# SAMD21_Xplained_Pro_EDBG.net
KiCad netlist of a schematic drawn in Altium Designer
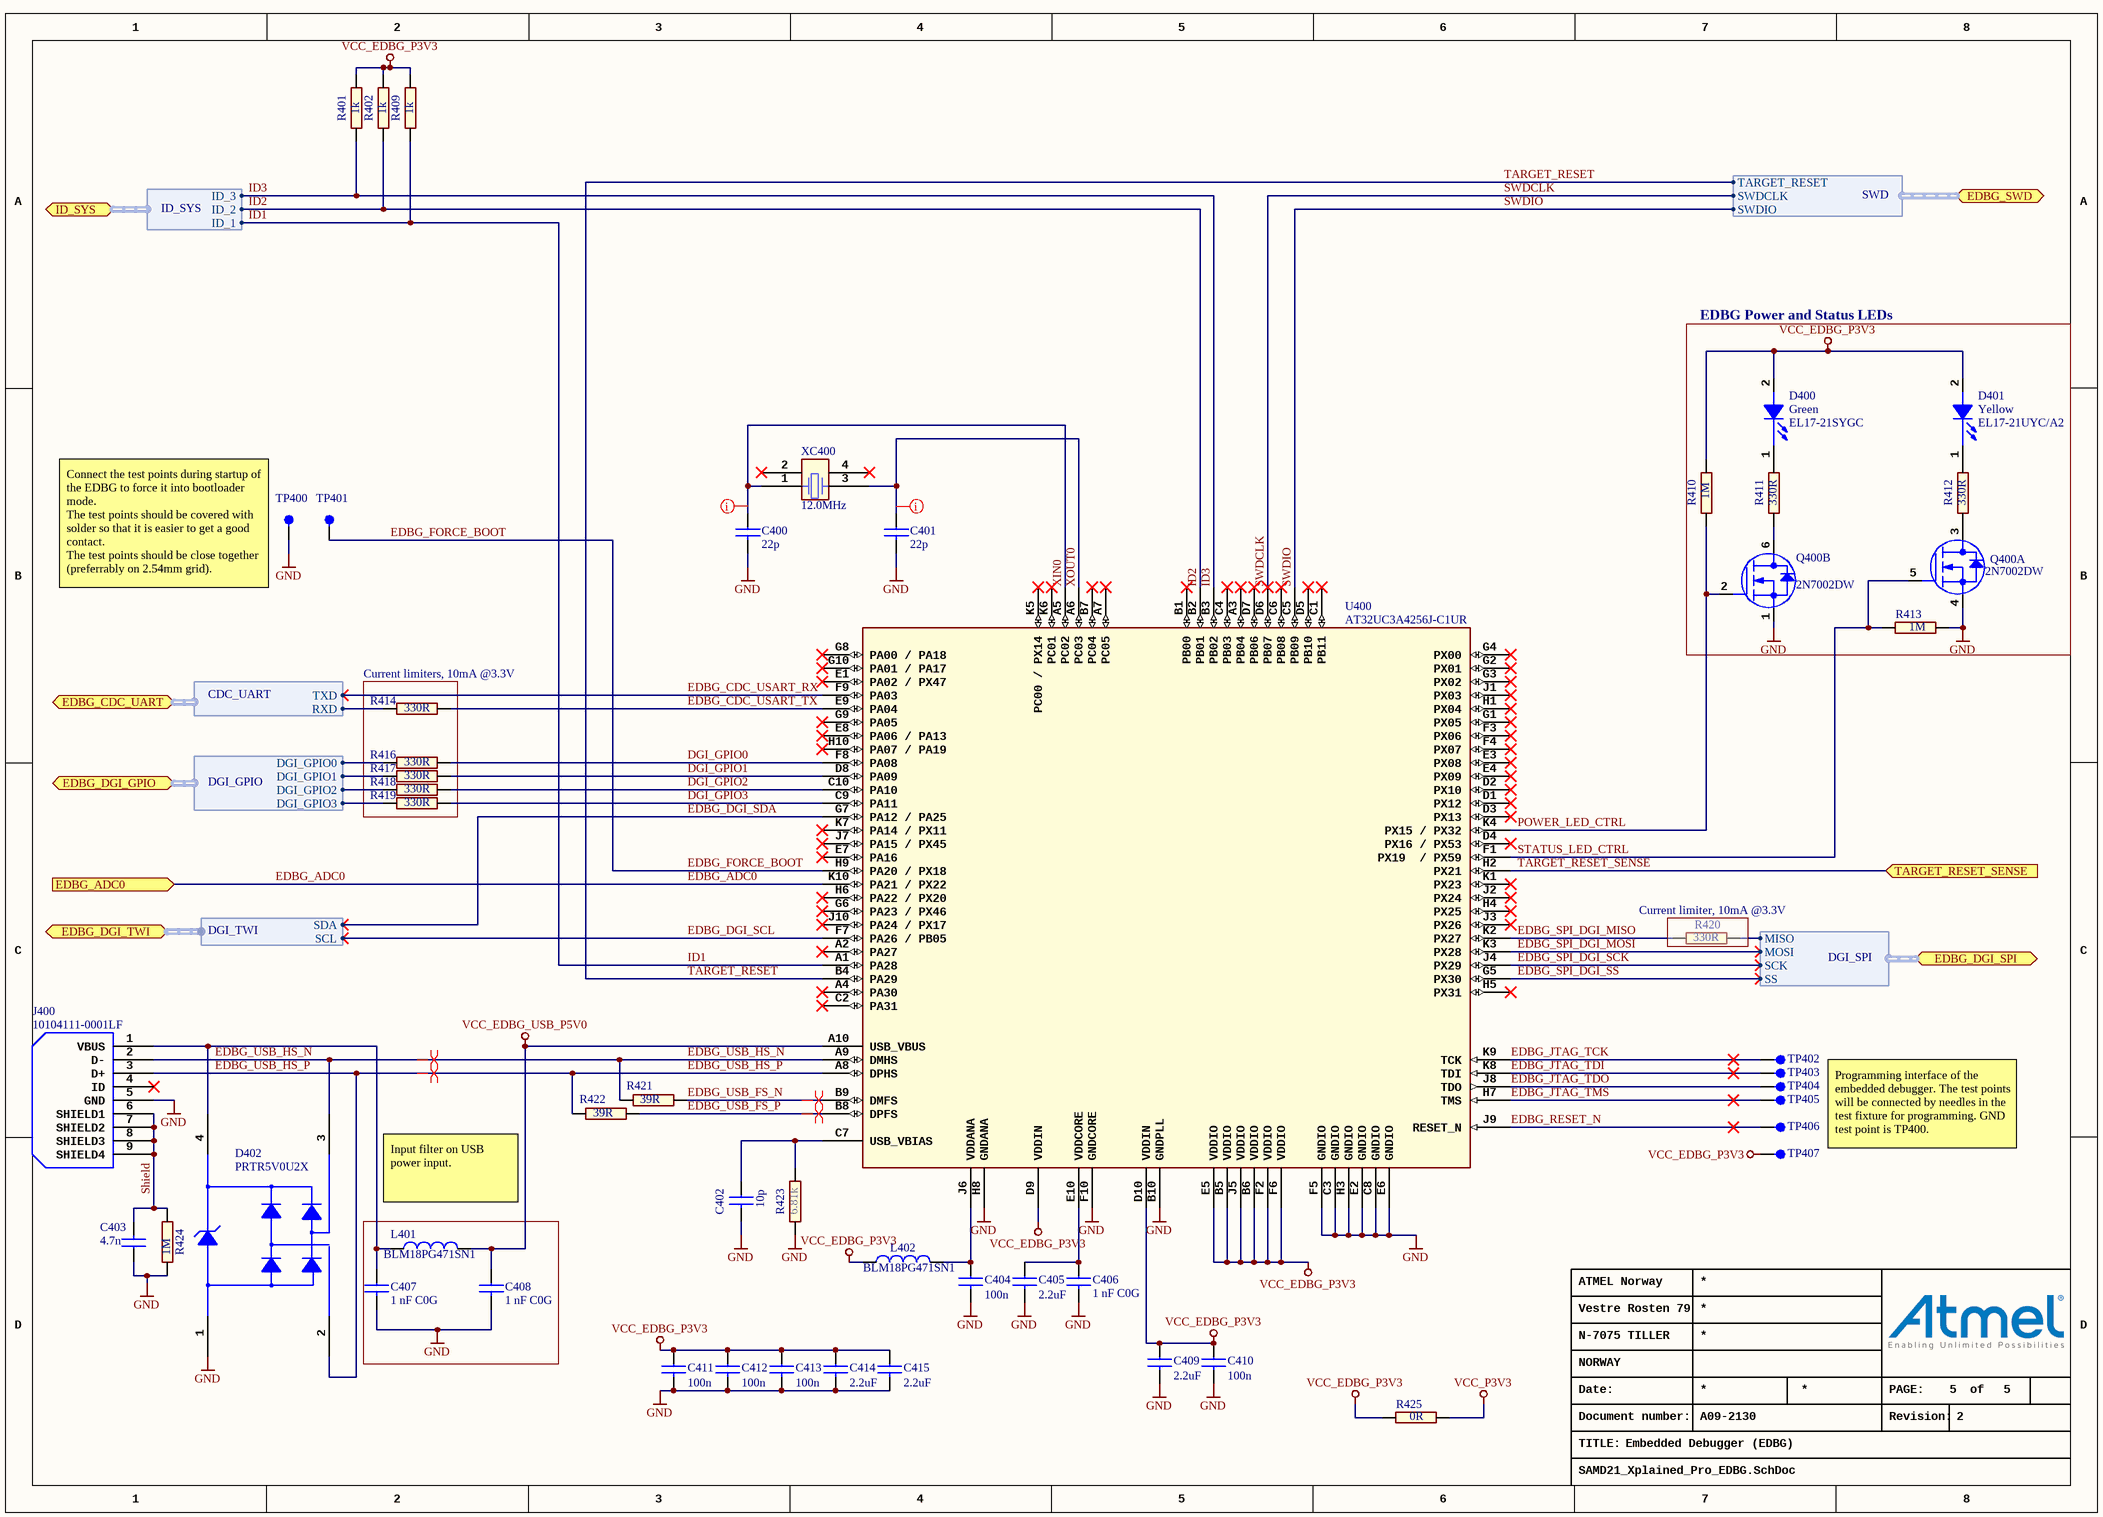
[diagram p0: SAMD21_Xplained_Pro_EDBG.SchDoc]

(export (version "E")
  (design (tool "Eeschema 10.0.6"))
  (components
    (comp (ref "C400")
      (value "22p")
      (footprint "AP1-00053")
      (description "Ceramic capacitor, SMD 0402, NP0, 50V, +/-5%")
      (fields (field (name "TOLERANCE") "50V, +/-5%"))
      (libsource (lib "AltiumDbLib") (part "CAP-NONPOL"))
    )
    (comp (ref "C401")
      (value "22p")
      (footprint "AP1-00053")
      (description "Ceramic capacitor, SMD 0402, NP0, 50V, +/-5%")
      (fields (field (name "TOLERANCE") "50V, +/-5%"))
      (libsource (lib "AltiumDbLib") (part "CAP-NONPOL"))
    )
    (comp (ref "C402")
      (value "10p")
      (footprint "AP1-00053")
      (description "Ceramic capacitor, SMD 0402, NP0, 50V, +/-5%")
      (fields (field (name "TOLERANCE") "50V, +/-5%"))
      (libsource (lib "AltiumDbLib") (part "CAP-NONPOL"))
    )
    (comp (ref "C403")
      (value "4.7n")
      (footprint "AP1-00053")
      (description "Ceramic capacitor, SMD 0402, X7R, 25V, +/-10%")
      (fields (field (name "TOLERANCE") "25V, +/-10%") (field (name "Comment") "CAP-NONPOL"))
      (libsource (lib "AltiumDbLib") (part "CAP-NONPOL"))
    )
    (comp (ref "C404")
      (value "100n")
      (footprint "AP1-00053")
      (description "Ceramic capacitor, SMD 0402, X7R, 16V, +/-10%")
      (fields (field (name "TOLERANCE") "16V, +/-10%") (field (name "MANUFACTURER") "Kemet"))
      (libsource (lib "AltiumDbLib") (part "CAP-NONPOL"))
    )
    (comp (ref "C405")
      (value "2.2uF")
      (footprint "AP1-00053")
      (description "Ceramic capacitor, SMD 0402, X5R, 6.3V, +/-20%")
      (fields (field (name "TOLERANCE") "±20%") (field (name "MANUFACTURER") "Kemet"))
      (libsource (lib "AltiumDbLib") (part "CAP-NONPOL"))
    )
    (comp (ref "C406")
      (value "1 nF C0G")
      (footprint "AP1-00053")
      (description "Ceramic capacitor, SMD 0402, C0G, 50V, +/-5%")
      (fields (field (name "TOLERANCE") "5%") (field (name "MANUFACTURER") "Murata"))
      (libsource (lib "AltiumDbLib") (part "CAP-NONPOL"))
    )
    (comp (ref "C407")
      (value "1 nF C0G")
      (footprint "AP1-00053")
      (description "Ceramic capacitor, SMD 0402, C0G, 50V, +/-5%")
      (fields (field (name "TOLERANCE") "5%") (field (name "MANUFACTURER") "Murata"))
      (libsource (lib "AltiumDbLib") (part "CAP-NONPOL"))
    )
    (comp (ref "C408")
      (value "1 nF C0G")
      (footprint "AP1-00053")
      (description "Ceramic capacitor, SMD 0402, C0G, 50V, +/-5%")
      (fields (field (name "TOLERANCE") "5%") (field (name "MANUFACTURER") "Murata"))
      (libsource (lib "AltiumDbLib") (part "CAP-NONPOL"))
    )
    (comp (ref "C409")
      (value "2.2uF")
      (footprint "AP1-00053")
      (description "Ceramic capacitor, SMD 0402, X5R, 6.3V, +/-20%")
      (fields (field (name "TOLERANCE") "±20%") (field (name "MANUFACTURER") "Kemet"))
      (libsource (lib "AltiumDbLib") (part "CAP-NONPOL"))
    )
    (comp (ref "C410")
      (value "100n")
      (footprint "AP1-00053")
      (description "Ceramic capacitor, SMD 0402, X7R, 16V, +/-10%")
      (fields (field (name "TOLERANCE") "16V, +/-10%") (field (name "MANUFACTURER") "Kemet"))
      (libsource (lib "AltiumDbLib") (part "CAP-NONPOL"))
    )
    (comp (ref "C411")
      (value "100n")
      (footprint "AP1-00053")
      (description "Ceramic capacitor, SMD 0402, X7R, 16V, +/-10%")
      (fields (field (name "TOLERANCE") "16V, +/-10%") (field (name "MANUFACTURER") "Kemet"))
      (libsource (lib "AltiumDbLib") (part "CAP-NONPOL"))
    )
    (comp (ref "C412")
      (value "100n")
      (footprint "AP1-00053")
      (description "Ceramic capacitor, SMD 0402, X7R, 16V, +/-10%")
      (fields (field (name "TOLERANCE") "16V, +/-10%") (field (name "MANUFACTURER") "Kemet"))
      (libsource (lib "AltiumDbLib") (part "CAP-NONPOL"))
    )
    (comp (ref "C413")
      (value "100n")
      (footprint "AP1-00053")
      (description "Ceramic capacitor, SMD 0402, X7R, 16V, +/-10%")
      (fields (field (name "TOLERANCE") "16V, +/-10%") (field (name "MANUFACTURER") "Kemet"))
      (libsource (lib "AltiumDbLib") (part "CAP-NONPOL"))
    )
    (comp (ref "C414")
      (value "2.2uF")
      (footprint "AP1-00053")
      (description "Ceramic capacitor, SMD 0402, X5R, 6.3V, +/-20%")
      (fields (field (name "TOLERANCE") "±20%") (field (name "MANUFACTURER") "Kemet"))
      (libsource (lib "AltiumDbLib") (part "CAP-NONPOL"))
    )
    (comp (ref "C415")
      (value "2.2uF")
      (footprint "AP1-00053")
      (description "Ceramic capacitor, SMD 0402, X5R, 6.3V, +/-20%")
      (fields (field (name "TOLERANCE") "±20%") (field (name "MANUFACTURER") "Kemet"))
      (libsource (lib "AltiumDbLib") (part "CAP-NONPOL"))
    )
    (comp (ref "D400")
      (value "Green")
      (footprint "AP4-00013")
      (description "LED, Green, Wave length=575nm, SMD 0805, ±70°")
      (fields
        (field (name "ALTIUM_VALUE") "EL17-21SYGC")
        (field (name "MANUFACTURER") "Everlight")
        (field (name "MPN") "EL17-21SYGC")
      )
      (libsource (lib "AltiumDbLib") (part "LED_12"))
    )
    (comp (ref "D401")
      (value "Yellow")
      (footprint "AP4-00013")
      (description "LED, Yellow, Wave length=591nm, SMD 0805, ±70°")
      (fields
        (field (name "ALTIUM_VALUE") "EL17-21UYC/A2")
        (field (name "MANUFACTURER") "Everlight")
        (field (name "MPN") "17-21UYC/S530-A3/TR8")
      )
      (libsource (lib "AltiumDbLib") (part "LED_12"))
    )
    (comp (ref "D402")
      (value "PRTR5V0U2X")
      (footprint "AP4-00001")
      (description "Double rail-to-rail USB ESD protection diode")
      (fields (field (name "MANUFACTURER") "Philips"))
      (libsource (lib "AltiumDbLib") (part "PRTR5V0U2X"))
    )
    (comp (ref "J400")
      (value "10104111-0001LF")
      (footprint "AP8-00604")
      (description "Micro USB AB Connector")
      (fields (field (name "MANUFACTURER") "FCI") (field (name "Comment") "USB_AB"))
      (libsource (lib "AltiumDbLib") (part "USB_AB"))
    )
    (comp (ref "L401")
      (value "BLM18PG471SN1")
      (footprint "AP3-00005")
      (description "SMD RF inductor 0603. Z=470Ohm (@100MHz), Max R(dc)=0.65Ohm, Max current=1A")
      (fields (field (name "TOLERANCE") "±25%") (field (name "MANUFACTURER") "Murata"))
      (libsource (lib "AltiumDbLib") (part "INDUCTOR"))
    )
    (comp (ref "L402")
      (value "BLM18PG471SN1")
      (footprint "AP3-00005")
      (description "SMD RF inductor 0603. Z=470Ohm (@100MHz), Max R(dc)=0.65Ohm, Max current=1A")
      (fields (field (name "TOLERANCE") "±25%") (field (name "MANUFACTURER") "Murata"))
      (libsource (lib "AltiumDbLib") (part "INDUCTOR"))
    )
    (comp (ref "Q400")
      (value "2N7002DW")
      (footprint "AP5-00001")
      (description "Dual N-Channel MOSFET, 60V, 115mA cont,RDS(ON) < 7.5 Ohm @50mA@5V, SOT-363")
      (fields
        (field (name "MANUFACTURER") "Fairchild")
        (field (name "Comment") "Same as 2N7002 but with two MOSFETs in one package")
      )
      (libsource (lib "AltiumDbLib") (part "MOSFET_DUAL_N_S2G2D1S1G1D2"))
    )
    (comp (ref "R401")
      (value "1k")
      (footprint "AP2-00000")
      (description "Thick film resistor, SMD 0402, 1/16W, 1%")
      (fields (field (name "TOLERANCE") "1 %") (field (name "Comment") "R2"))
      (libsource (lib "") (part "R2_4"))
    )
    (comp (ref "R402")
      (value "1k")
      (footprint "AP2-00000")
      (description "Thick film resistor, SMD 0402, 1/16W, 1%")
      (fields (field (name "TOLERANCE") "1 %") (field (name "Comment") "R2"))
      (libsource (lib "") (part "R2_4"))
    )
    (comp (ref "R409")
      (value "1k")
      (footprint "AP2-00000")
      (description "Thick film resistor, SMD 0402, 1/16W, 1%")
      (fields (field (name "TOLERANCE") "1 %") (field (name "Comment") "R2"))
      (libsource (lib "") (part "R2_4"))
    )
    (comp (ref "R410")
      (value "1M")
      (footprint "AP2-00000")
      (description "Thick film resistor, SMD 0402, 1/16W, 1%")
      (fields (field (name "TOLERANCE") "1 %") (field (name "MANUFACTURER") "KOA"))
      (libsource (lib "") (part "R2_4"))
    )
    (comp (ref "R411")
      (value "330R")
      (footprint "AP2-00000")
      (description "Thick film resistor, SMD 0402, 1/16W, 1%")
      (fields (field (name "TOLERANCE") "1 %") (field (name "Comment") "R2"))
      (libsource (lib "") (part "R2_4"))
    )
    (comp (ref "R412")
      (value "330R")
      (footprint "AP2-00000")
      (description "Thick film resistor, SMD 0402, 1/16W, 1%")
      (fields (field (name "TOLERANCE") "1 %") (field (name "Comment") "R2"))
      (libsource (lib "") (part "R2_4"))
    )
    (comp (ref "R413")
      (value "1M")
      (footprint "AP2-00000")
      (description "Thick film resistor, SMD 0402, 1/16W, 1%")
      (fields (field (name "TOLERANCE") "1 %") (field (name "MANUFACTURER") "KOA"))
      (libsource (lib "") (part "R2_3"))
    )
    (comp (ref "R414")
      (value "330R")
      (footprint "AP2-00000")
      (description "Thick film resistor, SMD 0402, 1/16W, 1%")
      (fields (field (name "TOLERANCE") "1 %") (field (name "Comment") "R2"))
      (libsource (lib "") (part "R2_1"))
    )
    (comp (ref "R416")
      (value "330R")
      (footprint "AP2-00000")
      (description "Thick film resistor, SMD 0402, 1/16W, 1%")
      (fields (field (name "TOLERANCE") "1 %") (field (name "Comment") "R2"))
      (libsource (lib "") (part "R2_1"))
    )
    (comp (ref "R417")
      (value "330R")
      (footprint "AP2-00000")
      (description "Thick film resistor, SMD 0402, 1/16W, 1%")
      (fields (field (name "TOLERANCE") "1 %") (field (name "Comment") "R2"))
      (libsource (lib "") (part "R2_1"))
    )
    (comp (ref "R418")
      (value "330R")
      (footprint "AP2-00000")
      (description "Thick film resistor, SMD 0402, 1/16W, 1%")
      (fields (field (name "TOLERANCE") "1 %") (field (name "Comment") "R2"))
      (libsource (lib "") (part "R2_1"))
    )
    (comp (ref "R419")
      (value "330R")
      (footprint "AP2-00000")
      (description "Thick film resistor, SMD 0402, 1/16W, 1%")
      (fields (field (name "TOLERANCE") "1 %") (field (name "Comment") "R2"))
      (libsource (lib "") (part "R2_1"))
    )
    (comp (ref "R420")
      (value "330R")
      (footprint "AP2-00000")
      (description "Thick film resistor, SMD 0402, 1/16W, 1%")
      (fields (field (name "TOLERANCE") "1 %") (field (name "Comment") "R2"))
      (libsource (lib "") (part "R2_1"))
    )
    (comp (ref "R421")
      (value "39R")
      (footprint "AP2-00011")
      (description "Thick film resistor, SMD 0402, 1/16W, 1%")
      (fields (field (name "TOLERANCE") "1 %") (field (name "Comment") "R2"))
      (libsource (lib "") (part "R2_2"))
    )
    (comp (ref "R422")
      (value "39R")
      (footprint "AP2-00011")
      (description "Thick film resistor, SMD 0402, 1/16W, 1%")
      (fields (field (name "TOLERANCE") "1 %") (field (name "Comment") "R2"))
      (libsource (lib "") (part "R2_2"))
    )
    (comp (ref "R423")
      (value "6.81k")
      (footprint "AP2-00011")
      (description "Thick film resistor, SMD 0402, 1/16W, 1%")
      (fields (field (name "TOLERANCE") "1%") (field (name "Comment") "R2"))
      (libsource (lib "") (part "R2_4"))
    )
    (comp (ref "R424")
      (value "1M")
      (footprint "AP2-00011")
      (description "Thick film resistor, SMD 0402, 1/16W, 1%")
      (fields (field (name "TOLERANCE") "1 %") (field (name "MANUFACTURER") "KOA"))
      (libsource (lib "AltiumDbLib") (part "R2"))
    )
    (comp (ref "R425")
      (value "0R")
      (footprint "AP2-00000")
      (description "Thick film resistor, SMD 0402, 1/16W, 1%")
      (fields (field (name "TOLERANCE") "1 %") (field (name "Comment") "R2"))
      (libsource (lib "") (part "R2_1"))
    )
    (comp (ref "TP400")
      (value "TESTPAD")
      (footprint "AP8-00010")
      (description "Single SMD testpad")
      (libsource (lib "AltiumDbLib") (part "TESTPOINT"))
    )
    (comp (ref "TP401")
      (value "TESTPAD")
      (footprint "AP8-00010")
      (description "Single SMD testpad")
      (libsource (lib "AltiumDbLib") (part "TESTPOINT"))
    )
    (comp (ref "TP402")
      (value "TESTPAD")
      (footprint "AP8-00010")
      (description "Single SMD testpad")
      (libsource (lib "AltiumDbLib") (part "TESTPOINT"))
    )
    (comp (ref "TP403")
      (value "TESTPAD")
      (footprint "AP8-00010")
      (description "Single SMD testpad")
      (libsource (lib "AltiumDbLib") (part "TESTPOINT"))
    )
    (comp (ref "TP404")
      (value "TESTPAD")
      (footprint "AP8-00010")
      (description "Single SMD testpad")
      (libsource (lib "AltiumDbLib") (part "TESTPOINT"))
    )
    (comp (ref "TP405")
      (value "TESTPAD")
      (footprint "AP8-00010")
      (description "Single SMD testpad")
      (libsource (lib "AltiumDbLib") (part "TESTPOINT"))
    )
    (comp (ref "TP406")
      (value "TESTPAD")
      (footprint "AP8-00010")
      (description "Single SMD testpad")
      (libsource (lib "AltiumDbLib") (part "TESTPOINT"))
    )
    (comp (ref "TP407")
      (value "TESTPAD")
      (footprint "AP8-00010")
      (description "Single SMD testpad")
      (libsource (lib "AltiumDbLib") (part "TESTPOINT"))
    )
    (comp (ref "U400")
      (value "AT32UC3A4256J-C1UR")
      (footprint "AP6-00206")
      (description "AVR 32-bit RISC MCU")
      (fields (field (name "MANUFACTURER") "ATMEL") (field (name "Comment") "100 ball VFBGA"))
      (libsource (lib "AltiumDbLib") (part "AT32UC3A4_VFBGA"))
    )
    (comp (ref "XC400")
      (value "12.0MHz")
      (footprint "AP7-00039")
      (description "Fox FQ5032B 12.0MHz SMD crystal 738B-12")
      (fields (field (name "TOLERANCE") "30PPM") (field (name "MANUFACTURER") "Fox  Electronics"))
      (libsource (lib "AltiumDbLib") (part "CRYSTAL1324"))
    )
  )
  (nets
    (net (code "7") (name "/DGI_GPIO0") (class "Default")
      (node (ref "R416") (pin "2") (pinfunction "2_2") (pintype "passive"))
      (node (ref "U400") (pin "F8") (pinfunction "PA08_F8") (pintype "bidirectional"))
    )
    (net (code "8") (name "/DGI_GPIO1") (class "Default")
      (node (ref "R417") (pin "2") (pinfunction "2_2") (pintype "passive"))
      (node (ref "U400") (pin "D8") (pinfunction "PA09_D8") (pintype "bidirectional"))
    )
    (net (code "9") (name "/DGI_GPIO2") (class "Default")
      (node (ref "R418") (pin "2") (pinfunction "2_2") (pintype "passive"))
      (node (ref "U400") (pin "C10") (pinfunction "PA10_C10") (pintype "bidirectional"))
    )
    (net (code "10") (name "/DGI_GPIO3") (class "Default")
      (node (ref "R419") (pin "2") (pinfunction "2_2") (pintype "passive"))
      (node (ref "U400") (pin "C9") (pinfunction "PA11_C9") (pintype "bidirectional"))
    )
    (net (code "11") (name "/EDBG_ADC0") (class "Default")
      (node (ref "U400") (pin "K10") (pinfunction "PA21_/_PX22_K10") (pintype "bidirectional"))
    )
    (net (code "12") (name "/EDBG_CDC_USART_RX") (class "Default")
      (node (ref "U400") (pin "F9") (pinfunction "PA03_F9") (pintype "bidirectional+no_connect"))
    )
    (net (code "13") (name "/EDBG_CDC_USART_TX") (class "Default")
      (node (ref "R414") (pin "2") (pinfunction "2_2") (pintype "passive"))
      (node (ref "U400") (pin "E9") (pinfunction "PA04_E9") (pintype "bidirectional"))
    )
    (net (code "14") (name "/EDBG_DGI_SCL") (class "Default")
      (node (ref "U400") (pin "F7") (pinfunction "PA26_/_PB05_F7") (pintype "bidirectional+no_connect"))
    )
    (net (code "15") (name "/EDBG_DGI_SDA") (class "Default")
      (node (ref "U400") (pin "G7") (pinfunction "PA12_/_PA25_G7") (pintype "bidirectional+no_connect"))
    )
    (net (code "16") (name "/EDBG_FORCE_BOOT") (class "Default")
      (node (ref "TP401") (pin "1") (pinfunction "1_1") (pintype "passive"))
      (node (ref "U400") (pin "H9") (pinfunction "PA20_/_PX18_H9") (pintype "bidirectional"))
    )
    (net (code "17") (name "/EDBG_JTAG_TCK") (class "Default")
      (node (ref "TP402") (pin "1") (pinfunction "1_1") (pintype "passive"))
      (node (ref "U400") (pin "K9") (pinfunction "TCK_K9") (pintype "input"))
    )
    (net (code "18") (name "/EDBG_JTAG_TDI") (class "Default")
      (node (ref "TP403") (pin "1") (pinfunction "1_1") (pintype "passive"))
      (node (ref "U400") (pin "K8") (pinfunction "TDI_K8") (pintype "input"))
    )
    (net (code "19") (name "/EDBG_JTAG_TDO") (class "Default")
      (node (ref "TP404") (pin "1") (pinfunction "1_1") (pintype "passive"))
      (node (ref "U400") (pin "J8") (pinfunction "TDO_J8") (pintype "output"))
    )
    (net (code "20") (name "/EDBG_JTAG_TMS") (class "Default")
      (node (ref "TP405") (pin "1") (pinfunction "1_1") (pintype "passive"))
      (node (ref "U400") (pin "H7") (pinfunction "TMS_H7") (pintype "input"))
    )
    (net (code "21") (name "/EDBG_RESET_N") (class "Default")
      (node (ref "TP406") (pin "1") (pinfunction "1_1") (pintype "passive"))
      (node (ref "U400") (pin "J9") (pinfunction "RESET_N_J9") (pintype "input"))
    )
    (net (code "22") (name "/EDBG_SPI_DGI_MISO") (class "Default")
      (node (ref "R420") (pin "1") (pinfunction "1_1") (pintype "passive"))
      (node (ref "U400") (pin "K2") (pinfunction "PX27_K2") (pintype "bidirectional"))
    )
    (net (code "23") (name "/EDBG_SPI_DGI_MOSI") (class "Default")
      (node (ref "U400") (pin "K3") (pinfunction "PX28_K3") (pintype "bidirectional+no_connect"))
    )
    (net (code "24") (name "/EDBG_SPI_DGI_SCK") (class "Default")
      (node (ref "U400") (pin "J4") (pinfunction "PX29_J4") (pintype "bidirectional+no_connect"))
    )
    (net (code "25") (name "/EDBG_SPI_DGI_SS") (class "Default")
      (node (ref "U400") (pin "G5") (pinfunction "PX30_G5") (pintype "bidirectional+no_connect"))
    )
    (net (code "26") (name "/EDBG_USB_FS_N") (class "Default")
      (node (ref "R421") (pin "2") (pinfunction "2_2") (pintype "passive"))
      (node (ref "U400") (pin "B9") (pinfunction "DMFS_B9") (pintype "bidirectional"))
    )
    (net (code "27") (name "/EDBG_USB_FS_P") (class "Default")
      (node (ref "R422") (pin "2") (pinfunction "2_2") (pintype "passive"))
      (node (ref "U400") (pin "B8") (pinfunction "DPFS_B8") (pintype "bidirectional"))
    )
    (net (code "28") (name "/EDBG_USB_HS_N") (class "Default")
      (node (ref "D402") (pin "3") (pinfunction "I/O_2_3") (pintype "passive"))
      (node (ref "J400") (pin "2") (pinfunction "D-_2") (pintype "passive"))
      (node (ref "R421") (pin "1") (pinfunction "1_1") (pintype "passive"))
      (node (ref "U400") (pin "A9") (pinfunction "DMHS_A9") (pintype "bidirectional"))
    )
    (net (code "29") (name "/EDBG_USB_HS_P") (class "Default")
      (node (ref "D402") (pin "2") (pinfunction "I/O_1_2") (pintype "passive"))
      (node (ref "J400") (pin "3") (pinfunction "D+_3") (pintype "passive"))
      (node (ref "R422") (pin "1") (pinfunction "1_1") (pintype "passive"))
      (node (ref "U400") (pin "A8") (pinfunction "DPHS_A8") (pintype "bidirectional"))
    )
    (net (code "30") (name "/ID1") (class "Default")
      (node (ref "R409") (pin "1") (pinfunction "1_1") (pintype "passive"))
      (node (ref "U400") (pin "A1") (pinfunction "PA28_A1") (pintype "bidirectional"))
    )
    (net (code "31") (name "/ID2") (class "Default")
      (node (ref "R402") (pin "1") (pinfunction "1_1") (pintype "passive"))
      (node (ref "U400") (pin "B2") (pinfunction "PB01_B2") (pintype "bidirectional"))
    )
    (net (code "32") (name "/ID3") (class "Default")
      (node (ref "R401") (pin "1") (pinfunction "1_1") (pintype "passive"))
      (node (ref "U400") (pin "B3") (pinfunction "PB02_B3") (pintype "bidirectional"))
    )
    (net (code "33") (name "/MISO") (class "Default")
      (node (ref "R420") (pin "2") (pinfunction "2_2") (pintype "passive"))
    )
    (net (code "34") (name "/POWER_LED_CTRL") (class "Default")
      (node (ref "Q400") (pin "2") (pinfunction "G2_2") (pintype "passive"))
      (node (ref "R410") (pin "1") (pinfunction "1_1") (pintype "passive"))
      (node (ref "U400") (pin "K4") (pinfunction "PX15_/_PX32_K4") (pintype "bidirectional"))
    )
    (net (code "35") (name "/RXD") (class "Default")
      (node (ref "R414") (pin "1") (pinfunction "1_1") (pintype "passive"))
    )
    (net (code "36") (name "/STATUS_LED_CTRL") (class "Default")
      (node (ref "Q400") (pin "5") (pinfunction "G1_5") (pintype "passive"))
      (node (ref "R413") (pin "2") (pinfunction "2_2") (pintype "passive"))
      (node (ref "U400") (pin "F1") (pinfunction "PX19__/_PX59_F1") (pintype "bidirectional"))
    )
    (net (code "37") (name "/SWDCLK") (class "Default")
      (node (ref "U400") (pin "D6") (pinfunction "PB07_D6") (pintype "bidirectional+no_connect"))
    )
    (net (code "38") (name "/SWDIO") (class "Default")
      (node (ref "U400") (pin "C5") (pinfunction "PB09_C5") (pintype "bidirectional"))
    )
    (net (code "39") (name "/Shield") (class "Default")
      (node (ref "C403") (pin "2") (pinfunction "2_2") (pintype "passive"))
      (node (ref "J400") (pin "6") (pinfunction "SHIELD1_6") (pintype "passive"))
      (node (ref "J400") (pin "7") (pinfunction "SHIELD2_7") (pintype "passive"))
      (node (ref "J400") (pin "8") (pinfunction "SHIELD3_8") (pintype "passive"))
      (node (ref "J400") (pin "9") (pinfunction "SHIELD4_9") (pintype "passive"))
      (node (ref "R424") (pin "2") (pinfunction "2_2") (pintype "passive"))
    )
    (net (code "40") (name "/TARGET_RESET") (class "Default")
      (node (ref "U400") (pin "B4") (pinfunction "PA29_B4") (pintype "bidirectional"))
    )
    (net (code "41") (name "/TARGET_RESET_SENSE") (class "Default")
      (node (ref "U400") (pin "H2") (pinfunction "PX21_H2") (pintype "bidirectional"))
    )
    (net (code "42") (name "/XIN0") (class "Default")
      (node (ref "C400") (pin "1") (pinfunction "1_1") (pintype "passive"))
      (node (ref "U400") (pin "A5") (pinfunction "PC02_A5") (pintype "bidirectional"))
      (node (ref "XC400") (pin "1") (pinfunction "1_1") (pintype "passive"))
    )
    (net (code "43") (name "/XOUT0") (class "Default")
      (node (ref "C401") (pin "1") (pinfunction "1_1") (pintype "passive"))
      (node (ref "U400") (pin "A6") (pinfunction "PC03_A6") (pintype "bidirectional"))
      (node (ref "XC400") (pin "3") (pinfunction "3_3") (pintype "passive"))
    )
    (net (code "50") (name "GND") (class "Default")
      (node (ref "C400") (pin "2") (pinfunction "2_2") (pintype "passive"))
      (node (ref "C401") (pin "2") (pinfunction "2_2") (pintype "passive"))
      (node (ref "C402") (pin "2") (pinfunction "2_2") (pintype "passive"))
      (node (ref "C403") (pin "1") (pinfunction "1_1") (pintype "passive"))
      (node (ref "C404") (pin "2") (pinfunction "2_2") (pintype "passive"))
      (node (ref "C405") (pin "2") (pinfunction "2_2") (pintype "passive"))
      (node (ref "C406") (pin "2") (pinfunction "2_2") (pintype "passive"))
      (node (ref "C407") (pin "2") (pinfunction "2_2") (pintype "passive"))
      (node (ref "C408") (pin "2") (pinfunction "2_2") (pintype "passive"))
      (node (ref "C409") (pin "2") (pinfunction "2_2") (pintype "passive"))
      (node (ref "C410") (pin "2") (pinfunction "2_2") (pintype "passive"))
      (node (ref "C411") (pin "2") (pinfunction "2_2") (pintype "passive"))
      (node (ref "C412") (pin "2") (pinfunction "2_2") (pintype "passive"))
      (node (ref "C413") (pin "2") (pinfunction "2_2") (pintype "passive"))
      (node (ref "C414") (pin "2") (pinfunction "2_2") (pintype "passive"))
      (node (ref "C415") (pin "2") (pinfunction "2_2") (pintype "passive"))
      (node (ref "D402") (pin "1") (pinfunction "GND_1") (pintype "passive"))
      (node (ref "J400") (pin "5") (pinfunction "GND_5") (pintype "passive"))
      (node (ref "Q400") (pin "1") (pinfunction "S2_1") (pintype "passive"))
      (node (ref "Q400") (pin "4") (pinfunction "S1_4") (pintype "passive"))
      (node (ref "R413") (pin "1") (pinfunction "1_1") (pintype "passive"))
      (node (ref "R423") (pin "1") (pinfunction "1_1") (pintype "passive"))
      (node (ref "R424") (pin "1") (pinfunction "1_1") (pintype "passive"))
      (node (ref "TP400") (pin "1") (pinfunction "1_1") (pintype "passive"))
      (node (ref "U400") (pin "B10") (pinfunction "GNDPLL_B10") (pintype "power_in"))
      (node (ref "U400") (pin "C3") (pinfunction "GNDIO_C3") (pintype "power_in"))
      (node (ref "U400") (pin "C8") (pinfunction "GNDIO_C8") (pintype "power_in"))
      (node (ref "U400") (pin "E2") (pinfunction "GNDIO_E2") (pintype "power_in"))
      (node (ref "U400") (pin "E6") (pinfunction "GNDIO_E6") (pintype "power_in"))
      (node (ref "U400") (pin "F10") (pinfunction "GNDCORE_F10") (pintype "power_in"))
      (node (ref "U400") (pin "F5") (pinfunction "GNDIO_F5") (pintype "power_in"))
      (node (ref "U400") (pin "H3") (pinfunction "GNDIO_H3") (pintype "power_in"))
      (node (ref "U400") (pin "H8") (pinfunction "GNDANA_H8") (pintype "power_in"))
    )
    (net (code "51") (name "Net-(D400-CATHODE)") (class "Default")
      (node (ref "D400") (pin "1") (pinfunction "CATHODE_1") (pintype "passive"))
      (node (ref "R411") (pin "2") (pinfunction "2_2") (pintype "passive"))
    )
    (net (code "52") (name "Net-(D401-CATHODE)") (class "Default")
      (node (ref "D401") (pin "1") (pinfunction "CATHODE_1") (pintype "passive"))
      (node (ref "R412") (pin "2") (pinfunction "2_2") (pintype "passive"))
    )
    (net (code "53") (name "Net-(D402-VCC)") (class "Default")
      (node (ref "C407") (pin "1") (pinfunction "1_1") (pintype "passive"))
      (node (ref "D402") (pin "4") (pinfunction "VCC_4") (pintype "passive"))
      (node (ref "J400") (pin "1") (pinfunction "VBUS_1") (pintype "passive"))
      (node (ref "L401") (pin "1") (pinfunction "1_1") (pintype "passive"))
    )
    (net (code "54") (name "Net-(Q400A-D1)") (class "Default")
      (node (ref "Q400") (pin "3") (pinfunction "D1_3") (pintype "passive"))
      (node (ref "R412") (pin "1") (pinfunction "1_1") (pintype "passive"))
    )
    (net (code "55") (name "Net-(Q400B-D2)") (class "Default")
      (node (ref "Q400") (pin "6") (pinfunction "D2_6") (pintype "passive"))
      (node (ref "R411") (pin "1") (pinfunction "1_1") (pintype "passive"))
    )
    (net (code "56") (name "Net-(U400-USB_VBIAS)") (class "Default")
      (node (ref "C402") (pin "1") (pinfunction "1_1") (pintype "passive"))
      (node (ref "R423") (pin "2") (pinfunction "2_2") (pintype "passive"))
      (node (ref "U400") (pin "C7") (pinfunction "USB_VBIAS_C7") (pintype "power_in"))
    )
    (net (code "57") (name "Net-(U400-VDDANA)") (class "Default")
      (node (ref "C404") (pin "1") (pinfunction "1_1") (pintype "passive"))
      (node (ref "L402") (pin "2") (pinfunction "2_2") (pintype "passive"))
      (node (ref "U400") (pin "J6") (pinfunction "VDDANA_J6") (pintype "power_in"))
    )
    (net (code "58") (name "Net-(U400-VDDCORE)") (class "Default")
      (node (ref "C405") (pin "1") (pinfunction "1_1") (pintype "passive"))
      (node (ref "C406") (pin "1") (pinfunction "1_1") (pintype "passive"))
      (node (ref "U400") (pin "E10") (pinfunction "VDDCORE_E10") (pintype "power_in"))
    )
    (net (code "59") (name "VCC_EDBG_P3V3") (class "Default")
      (node (ref "C409") (pin "1") (pinfunction "1_1") (pintype "passive"))
      (node (ref "C410") (pin "1") (pinfunction "1_1") (pintype "passive"))
      (node (ref "C411") (pin "1") (pinfunction "1_1") (pintype "passive"))
      (node (ref "C412") (pin "1") (pinfunction "1_1") (pintype "passive"))
      (node (ref "C413") (pin "1") (pinfunction "1_1") (pintype "passive"))
      (node (ref "C414") (pin "1") (pinfunction "1_1") (pintype "passive"))
      (node (ref "C415") (pin "1") (pinfunction "1_1") (pintype "passive"))
      (node (ref "D400") (pin "2") (pinfunction "ANODE_2") (pintype "passive"))
      (node (ref "D401") (pin "2") (pinfunction "ANODE_2") (pintype "passive"))
      (node (ref "L402") (pin "1") (pinfunction "1_1") (pintype "passive"))
      (node (ref "R401") (pin "2") (pinfunction "2_2") (pintype "passive"))
      (node (ref "R402") (pin "2") (pinfunction "2_2") (pintype "passive"))
      (node (ref "R409") (pin "2") (pinfunction "2_2") (pintype "passive"))
      (node (ref "R410") (pin "2") (pinfunction "2_2") (pintype "passive"))
      (node (ref "R425") (pin "1") (pinfunction "1_1") (pintype "passive"))
      (node (ref "TP407") (pin "1") (pinfunction "1_1") (pintype "passive"))
      (node (ref "U400") (pin "B5") (pinfunction "VDDIO_B5") (pintype "power_in"))
      (node (ref "U400") (pin "B6") (pinfunction "VDDIO_B6") (pintype "power_in"))
      (node (ref "U400") (pin "D10") (pinfunction "VDDIN_D10") (pintype "power_in"))
      (node (ref "U400") (pin "D9") (pinfunction "VDDIN_D9") (pintype "power_in"))
      (node (ref "U400") (pin "E5") (pinfunction "VDDIO_E5") (pintype "power_in"))
      (node (ref "U400") (pin "F2") (pinfunction "VDDIO_F2") (pintype "power_in"))
      (node (ref "U400") (pin "F6") (pinfunction "VDDIO_F6") (pintype "power_in"))
      (node (ref "U400") (pin "J5") (pinfunction "VDDIO_J5") (pintype "power_in"))
    )
    (net (code "60") (name "VCC_EDBG_USB_P5V0") (class "Default")
      (node (ref "C408") (pin "1") (pinfunction "1_1") (pintype "passive"))
      (node (ref "L401") (pin "2") (pinfunction "2_2") (pintype "passive"))
      (node (ref "U400") (pin "A10") (pinfunction "USB_VBUS_A10") (pintype "power_in"))
    )
    (net (code "61") (name "VCC_P3V3") (class "Default")
      (node (ref "R425") (pin "2") (pinfunction "2_2") (pintype "passive"))
    )
    (net (code "62") (name "unconnected-(J400-ID-Pad4)") (class "Default")
      (node (ref "J400") (pin "4") (pinfunction "ID_4") (pintype "passive+no_connect"))
    )
    (net (code "63") (name "unconnected-(R416-Pad1)") (class "Default")
      (node (ref "R416") (pin "1") (pinfunction "1_1") (pintype "passive"))
    )
    (net (code "64") (name "unconnected-(R417-Pad1)") (class "Default")
      (node (ref "R417") (pin "1") (pinfunction "1_1") (pintype "passive"))
    )
    (net (code "65") (name "unconnected-(R418-Pad1)") (class "Default")
      (node (ref "R418") (pin "1") (pinfunction "1_1") (pintype "passive"))
    )
    (net (code "66") (name "unconnected-(R419-Pad1)") (class "Default")
      (node (ref "R419") (pin "1") (pinfunction "1_1") (pintype "passive"))
    )
    (net (code "67") (name "unconnected-(U400-PA00_{slash}_PA18-PadG8)") (class "Default")
      (node (ref "U400") (pin "G8") (pinfunction "PA00_/_PA18_G8") (pintype "bidirectional+no_connect"))
    )
    (net (code "68") (name "unconnected-(U400-PA01_{slash}_PA17-PadG10)") (class "Default")
      (node (ref "U400") (pin "G10") (pinfunction "PA01_/_PA17_G10") (pintype "bidirectional+no_connect"))
    )
    (net (code "69") (name "unconnected-(U400-PA02_{slash}_PX47-PadE1)") (class "Default")
      (node (ref "U400") (pin "E1") (pinfunction "PA02_/_PX47_E1") (pintype "bidirectional+no_connect"))
    )
    (net (code "70") (name "unconnected-(U400-PA05-PadG9)") (class "Default")
      (node (ref "U400") (pin "G9") (pinfunction "PA05_G9") (pintype "bidirectional+no_connect"))
    )
    (net (code "71") (name "unconnected-(U400-PA06_{slash}_PA13-PadE8)") (class "Default")
      (node (ref "U400") (pin "E8") (pinfunction "PA06_/_PA13_E8") (pintype "bidirectional+no_connect"))
    )
    (net (code "72") (name "unconnected-(U400-PA07_{slash}_PA19-PadH10)") (class "Default")
      (node (ref "U400") (pin "H10") (pinfunction "PA07_/_PA19_H10") (pintype "bidirectional+no_connect"))
    )
    (net (code "73") (name "unconnected-(U400-PA14_{slash}_PX11-PadK7)") (class "Default")
      (node (ref "U400") (pin "K7") (pinfunction "PA14_/_PX11_K7") (pintype "bidirectional+no_connect"))
    )
    (net (code "74") (name "unconnected-(U400-PA15_{slash}_PX45-PadJ7)") (class "Default")
      (node (ref "U400") (pin "J7") (pinfunction "PA15_/_PX45_J7") (pintype "bidirectional+no_connect"))
    )
    (net (code "75") (name "unconnected-(U400-PA16-PadE7)") (class "Default")
      (node (ref "U400") (pin "E7") (pinfunction "PA16_E7") (pintype "bidirectional+no_connect"))
    )
    (net (code "76") (name "unconnected-(U400-PA22_{slash}_PX20-PadH6)") (class "Default")
      (node (ref "U400") (pin "H6") (pinfunction "PA22_/_PX20_H6") (pintype "bidirectional+no_connect"))
    )
    (net (code "77") (name "unconnected-(U400-PA23_{slash}_PX46-PadG6)") (class "Default")
      (node (ref "U400") (pin "G6") (pinfunction "PA23_/_PX46_G6") (pintype "bidirectional+no_connect"))
    )
    (net (code "78") (name "unconnected-(U400-PA24_{slash}_PX17-PadJ10)") (class "Default")
      (node (ref "U400") (pin "J10") (pinfunction "PA24_/_PX17_J10") (pintype "bidirectional+no_connect"))
    )
    (net (code "79") (name "unconnected-(U400-PA27-PadA2)") (class "Default")
      (node (ref "U400") (pin "A2") (pinfunction "PA27_A2") (pintype "bidirectional+no_connect"))
    )
    (net (code "80") (name "unconnected-(U400-PA30-PadA4)") (class "Default")
      (node (ref "U400") (pin "A4") (pinfunction "PA30_A4") (pintype "bidirectional+no_connect"))
    )
    (net (code "81") (name "unconnected-(U400-PA31-PadC2)") (class "Default")
      (node (ref "U400") (pin "C2") (pinfunction "PA31_C2") (pintype "bidirectional+no_connect"))
    )
    (net (code "82") (name "unconnected-(U400-PB00-PadB1)") (class "Default")
      (node (ref "U400") (pin "B1") (pinfunction "PB00_B1") (pintype "bidirectional+no_connect"))
    )
    (net (code "83") (name "unconnected-(U400-PB03-PadC4)") (class "Default")
      (node (ref "U400") (pin "C4") (pinfunction "PB03_C4") (pintype "bidirectional+no_connect"))
    )
    (net (code "84") (name "unconnected-(U400-PB04-PadA3)") (class "Default")
      (node (ref "U400") (pin "A3") (pinfunction "PB04_A3") (pintype "bidirectional+no_connect"))
    )
    (net (code "85") (name "unconnected-(U400-PB06-PadD7)") (class "Default")
      (node (ref "U400") (pin "D7") (pinfunction "PB06_D7") (pintype "bidirectional+no_connect"))
    )
    (net (code "86") (name "unconnected-(U400-PB08-PadC6)") (class "Default")
      (node (ref "U400") (pin "C6") (pinfunction "PB08_C6") (pintype "bidirectional+no_connect"))
    )
    (net (code "87") (name "unconnected-(U400-PB10-PadD5)") (class "Default")
      (node (ref "U400") (pin "D5") (pinfunction "PB10_D5") (pintype "bidirectional+no_connect"))
    )
    (net (code "88") (name "unconnected-(U400-PB11-PadC1)") (class "Default")
      (node (ref "U400") (pin "C1") (pinfunction "PB11_C1") (pintype "bidirectional+no_connect"))
    )
    (net (code "89") (name "unconnected-(U400-PC00_{slash}_PX14-PadK5)") (class "Default")
      (node (ref "U400") (pin "K5") (pinfunction "PC00_/_PX14_K5") (pintype "bidirectional+no_connect"))
    )
    (net (code "90") (name "unconnected-(U400-PC01-PadK6)") (class "Default")
      (node (ref "U400") (pin "K6") (pinfunction "PC01_K6") (pintype "bidirectional+no_connect"))
    )
    (net (code "91") (name "unconnected-(U400-PC04-PadB7)") (class "Default")
      (node (ref "U400") (pin "B7") (pinfunction "PC04_B7") (pintype "bidirectional+no_connect"))
    )
    (net (code "92") (name "unconnected-(U400-PC05-PadA7)") (class "Default")
      (node (ref "U400") (pin "A7") (pinfunction "PC05_A7") (pintype "bidirectional+no_connect"))
    )
    (net (code "93") (name "unconnected-(U400-PX00-PadG4)") (class "Default")
      (node (ref "U400") (pin "G4") (pinfunction "PX00_G4") (pintype "bidirectional+no_connect"))
    )
    (net (code "94") (name "unconnected-(U400-PX01-PadG2)") (class "Default")
      (node (ref "U400") (pin "G2") (pinfunction "PX01_G2") (pintype "bidirectional+no_connect"))
    )
    (net (code "95") (name "unconnected-(U400-PX02-PadG3)") (class "Default")
      (node (ref "U400") (pin "G3") (pinfunction "PX02_G3") (pintype "bidirectional+no_connect"))
    )
    (net (code "96") (name "unconnected-(U400-PX03-PadJ1)") (class "Default")
      (node (ref "U400") (pin "J1") (pinfunction "PX03_J1") (pintype "bidirectional+no_connect"))
    )
    (net (code "97") (name "unconnected-(U400-PX04-PadH1)") (class "Default")
      (node (ref "U400") (pin "H1") (pinfunction "PX04_H1") (pintype "bidirectional+no_connect"))
    )
    (net (code "98") (name "unconnected-(U400-PX05-PadG1)") (class "Default")
      (node (ref "U400") (pin "G1") (pinfunction "PX05_G1") (pintype "bidirectional+no_connect"))
    )
    (net (code "99") (name "unconnected-(U400-PX06-PadF3)") (class "Default")
      (node (ref "U400") (pin "F3") (pinfunction "PX06_F3") (pintype "bidirectional+no_connect"))
    )
    (net (code "100") (name "unconnected-(U400-PX07-PadF4)") (class "Default")
      (node (ref "U400") (pin "F4") (pinfunction "PX07_F4") (pintype "bidirectional+no_connect"))
    )
    (net (code "101") (name "unconnected-(U400-PX08-PadE3)") (class "Default")
      (node (ref "U400") (pin "E3") (pinfunction "PX08_E3") (pintype "bidirectional+no_connect"))
    )
    (net (code "102") (name "unconnected-(U400-PX09-PadE4)") (class "Default")
      (node (ref "U400") (pin "E4") (pinfunction "PX09_E4") (pintype "bidirectional+no_connect"))
    )
    (net (code "103") (name "unconnected-(U400-PX10-PadD2)") (class "Default")
      (node (ref "U400") (pin "D2") (pinfunction "PX10_D2") (pintype "bidirectional+no_connect"))
    )
    (net (code "104") (name "unconnected-(U400-PX12-PadD1)") (class "Default")
      (node (ref "U400") (pin "D1") (pinfunction "PX12_D1") (pintype "bidirectional+no_connect"))
    )
    (net (code "105") (name "unconnected-(U400-PX13-PadD3)") (class "Default")
      (node (ref "U400") (pin "D3") (pinfunction "PX13_D3") (pintype "bidirectional+no_connect"))
    )
    (net (code "106") (name "unconnected-(U400-PX16_{slash}_PX53-PadD4)") (class "Default")
      (node (ref "U400") (pin "D4") (pinfunction "PX16_/_PX53_D4") (pintype "bidirectional+no_connect"))
    )
    (net (code "107") (name "unconnected-(U400-PX23-PadK1)") (class "Default")
      (node (ref "U400") (pin "K1") (pinfunction "PX23_K1") (pintype "bidirectional+no_connect"))
    )
    (net (code "108") (name "unconnected-(U400-PX24-PadJ2)") (class "Default")
      (node (ref "U400") (pin "J2") (pinfunction "PX24_J2") (pintype "bidirectional+no_connect"))
    )
    (net (code "109") (name "unconnected-(U400-PX25-PadH4)") (class "Default")
      (node (ref "U400") (pin "H4") (pinfunction "PX25_H4") (pintype "bidirectional+no_connect"))
    )
    (net (code "110") (name "unconnected-(U400-PX26-PadJ3)") (class "Default")
      (node (ref "U400") (pin "J3") (pinfunction "PX26_J3") (pintype "bidirectional+no_connect"))
    )
    (net (code "111") (name "unconnected-(U400-PX31-PadH5)") (class "Default")
      (node (ref "U400") (pin "H5") (pinfunction "PX31_H5") (pintype "bidirectional+no_connect"))
    )
    (net (code "112") (name "unconnected-(XC400-Pad2)") (class "Default")
      (node (ref "XC400") (pin "2") (pinfunction "2_2") (pintype "passive+no_connect"))
    )
    (net (code "113") (name "unconnected-(XC400-Pad4)") (class "Default")
      (node (ref "XC400") (pin "4") (pinfunction "4_4") (pintype "passive+no_connect"))
    )
  )
)
